# LNA-SMA.net
KiCad netlist of a schematic drawn in EAGLE
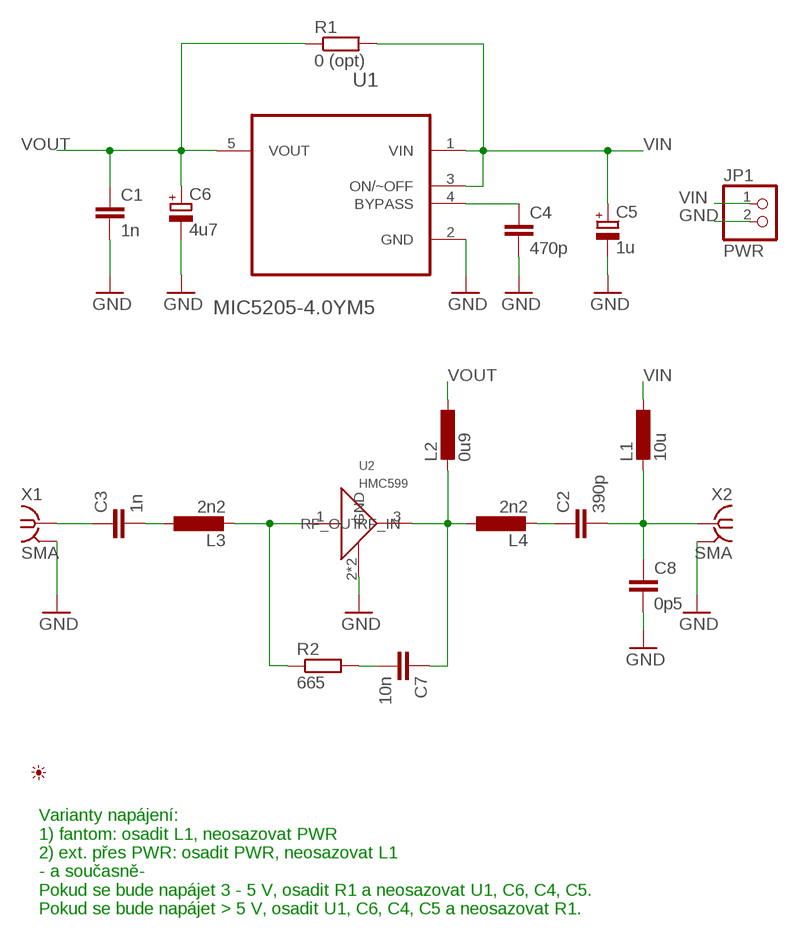
[diagram p0: schematic, sheet 1]

(export (version "E")
  (design (tool "Eeschema 10.0.6"))
  (components
    (comp (ref "C1")
      (value "1n")
      (footprint "eagle-import:C0603")
      (libsource (lib "eagle-import") (part "C-EUC0603"))
    )
    (comp (ref "C2")
      (value "390p")
      (footprint "eagle-import:C0603")
      (libsource (lib "eagle-import") (part "C-EUC0603"))
    )
    (comp (ref "C3")
      (value "1n")
      (footprint "eagle-import:C0603")
      (libsource (lib "eagle-import") (part "C-EUC0603"))
    )
    (comp (ref "C4")
      (value "470p")
      (footprint "eagle-import:C0603")
      (libsource (lib "eagle-import") (part "C-EUC0603"))
    )
    (comp (ref "C5")
      (value "1u")
      (footprint "eagle-import:SMC_A")
      (libsource (lib "eagle-import") (part "CPOL-EUSMCA"))
    )
    (comp (ref "C6")
      (value "4u7")
      (footprint "eagle-import:SMC_A")
      (libsource (lib "eagle-import") (part "CPOL-EUSMCA"))
    )
    (comp (ref "C7")
      (value "10n")
      (footprint "eagle-import:C0603")
      (libsource (lib "eagle-import") (part "C-EUC0603"))
    )
    (comp (ref "C8")
      (value "0p5")
      (footprint "eagle-import:C0603")
      (libsource (lib "eagle-import") (part "C-EUC0603"))
    )
    (comp (ref "JP1")
      (value "PWR")
      (footprint "eagle-import:1X02")
      (libsource (lib "eagle-import") (part "PINHD-1X2"))
    )
    (comp (ref "L1")
      (value "10u")
      (footprint "eagle-import:L2012C")
      (libsource (lib "eagle-import") (part "L-EUL2012C"))
    )
    (comp (ref "L2")
      (value "0u9")
      (footprint "eagle-import:L2012C")
      (libsource (lib "eagle-import") (part "L-EUL2012C"))
    )
    (comp (ref "L3")
      (value "2n2")
      (footprint "eagle-import:L2012C")
      (libsource (lib "eagle-import") (part "L-EUL2012C"))
    )
    (comp (ref "L4")
      (value "2n2")
      (footprint "eagle-import:L2012C")
      (libsource (lib "eagle-import") (part "L-EUL2012C"))
    )
    (comp (ref "R1")
      (value "0 (opt)")
      (footprint "eagle-import:R0603")
      (libsource (lib "eagle-import") (part "R-EU_R0603"))
    )
    (comp (ref "R2")
      (value "665")
      (footprint "eagle-import:R0603")
      (libsource (lib "eagle-import") (part "R-EU_R0603"))
    )
    (comp (ref "U$1")
      (value "PICTO_1")
      (footprint "eagle-import:PICTO_1")
      (libsource (lib "eagle-import") (part "PICTO_1"))
    )
    (comp (ref "U1")
      (value "MIC5205-4.0YM5")
      (footprint "eagle-import:SOT95P280X145-5N")
      (fields (field (name "MPN") "LP2985A-18DBVJ"))
      (libsource (lib "eagle-import") (part "LP2985A-18DBVJ"))
    )
    (comp (ref "U2")
      (value "HMC599")
      (footprint "eagle-import:SOT89")
      (libsource (lib "eagle-import") (part "HMC599"))
    )
    (comp (ref "X1")
      (value "SMA")
      (footprint "eagle-import:J502-ND-142-0701-801_806")
      (fields (field (name "MF") "JOHNSON COMPONENTS") (field (name "MPN") "142-0701-801"))
      (libsource (lib "eagle-import") (part "SMA-142-0701-801/806"))
    )
    (comp (ref "X2")
      (value "SMA")
      (footprint "eagle-import:J502-ND-142-0701-801_806")
      (fields (field (name "MF") "JOHNSON COMPONENTS") (field (name "MPN") "142-0701-801"))
      (libsource (lib "eagle-import") (part "SMA-142-0701-801/806"))
    )
  )
  (nets
    (net (code "1") (name "/VIN") (class "Default")
      (node (ref "C5") (pin "+") (pinfunction "+_+") (pintype "passive"))
      (node (ref "JP1") (pin "1") (pinfunction "1_1") (pintype "passive"))
      (node (ref "L1") (pin "1") (pinfunction "1_1") (pintype "passive"))
      (node (ref "R1") (pin "2") (pinfunction "2_2") (pintype "passive"))
      (node (ref "U1") (pin "1") (pinfunction "VIN_1") (pintype "input"))
      (node (ref "U1") (pin "3") (pinfunction "ON/~{OFF}_3") (pintype "input"))
    )
    (net (code "2") (name "/VOUT") (class "Default")
      (node (ref "C1") (pin "1") (pinfunction "1_1") (pintype "passive"))
      (node (ref "C6") (pin "+") (pinfunction "+_+") (pintype "passive"))
      (node (ref "L2") (pin "1") (pinfunction "1_1") (pintype "passive"))
      (node (ref "R1") (pin "1") (pinfunction "1_1") (pintype "passive"))
      (node (ref "U1") (pin "5") (pinfunction "VOUT_5") (pintype "output"))
    )
    (net (code "3") (name "GND") (class "Default")
      (node (ref "C1") (pin "2") (pinfunction "2_2") (pintype "passive"))
      (node (ref "C4") (pin "2") (pinfunction "2_2") (pintype "passive"))
      (node (ref "C5") (pin "-") (pinfunction "-_-") (pintype "passive"))
      (node (ref "C6") (pin "-") (pinfunction "-_-") (pintype "passive"))
      (node (ref "C8") (pin "2") (pinfunction "2_2") (pintype "passive"))
      (node (ref "JP1") (pin "2") (pinfunction "2_2") (pintype "passive"))
      (node (ref "U1") (pin "2") (pinfunction "GND_2") (pintype "passive"))
      (node (ref "U2") (pin "2") (pinfunction "GND_2") (pintype "power_in"))
      (node (ref "U2") (pin "2.1") (pinfunction "GND_2.1") (pintype "power_in"))
      (node (ref "X1") (pin "G@1") (pinfunction "2_G@1") (pintype "passive"))
      (node (ref "X1") (pin "G@2") (pinfunction "2_G@2") (pintype "passive"))
      (node (ref "X1") (pin "G@3") (pinfunction "2_G@3") (pintype "passive"))
      (node (ref "X1") (pin "G@4") (pinfunction "2_G@4") (pintype "passive"))
      (node (ref "X2") (pin "G@1") (pinfunction "2_G@1") (pintype "passive"))
      (node (ref "X2") (pin "G@2") (pinfunction "2_G@2") (pintype "passive"))
      (node (ref "X2") (pin "G@3") (pinfunction "2_G@3") (pintype "passive"))
      (node (ref "X2") (pin "G@4") (pinfunction "2_G@4") (pintype "passive"))
    )
    (net (code "4") (name "Net-(C2-Pad1)") (class "Default")
      (node (ref "C2") (pin "1") (pinfunction "1_1") (pintype "passive"))
      (node (ref "L4") (pin "2") (pinfunction "2_2") (pintype "passive"))
    )
    (net (code "5") (name "Net-(C2-Pad2)") (class "Default")
      (node (ref "C2") (pin "2") (pinfunction "2_2") (pintype "passive"))
      (node (ref "C8") (pin "1") (pinfunction "1_1") (pintype "passive"))
      (node (ref "L1") (pin "2") (pinfunction "2_2") (pintype "passive"))
      (node (ref "X2") (pin "1") (pinfunction "1_1") (pintype "passive"))
    )
    (net (code "6") (name "Net-(C3-Pad1)") (class "Default")
      (node (ref "C3") (pin "1") (pinfunction "1_1") (pintype "passive"))
      (node (ref "X1") (pin "1") (pinfunction "1_1") (pintype "passive"))
    )
    (net (code "7") (name "Net-(C3-Pad2)") (class "Default")
      (node (ref "C3") (pin "2") (pinfunction "2_2") (pintype "passive"))
      (node (ref "L3") (pin "1") (pinfunction "1_1") (pintype "passive"))
    )
    (net (code "8") (name "Net-(C7-Pad2)") (class "Default")
      (node (ref "C7") (pin "2") (pinfunction "2_2") (pintype "passive"))
      (node (ref "R2") (pin "2") (pinfunction "2_2") (pintype "passive"))
    )
    (net (code "9") (name "Net-(U1-BYPASS)") (class "Default")
      (node (ref "C4") (pin "1") (pinfunction "1_1") (pintype "passive"))
      (node (ref "U1") (pin "4") (pinfunction "BYPASS_4") (pintype "input"))
    )
    (net (code "10") (name "Net-(U2-RF_IN)") (class "Default")
      (node (ref "L3") (pin "2") (pinfunction "2_2") (pintype "passive"))
      (node (ref "R2") (pin "1") (pinfunction "1_1") (pintype "passive"))
      (node (ref "U2") (pin "1") (pinfunction "RF_IN_1") (pintype "input"))
    )
    (net (code "11") (name "Net-(U2-RF_OUT)") (class "Default")
      (node (ref "C7") (pin "1") (pinfunction "1_1") (pintype "passive"))
      (node (ref "L2") (pin "2") (pinfunction "2_2") (pintype "passive"))
      (node (ref "L4") (pin "1") (pinfunction "1_1") (pintype "passive"))
      (node (ref "U2") (pin "3") (pinfunction "RF_OUT_3") (pintype "output"))
    )
  )
)
